# design.net
KiCad netlist of a schematic drawn in Altium Designer
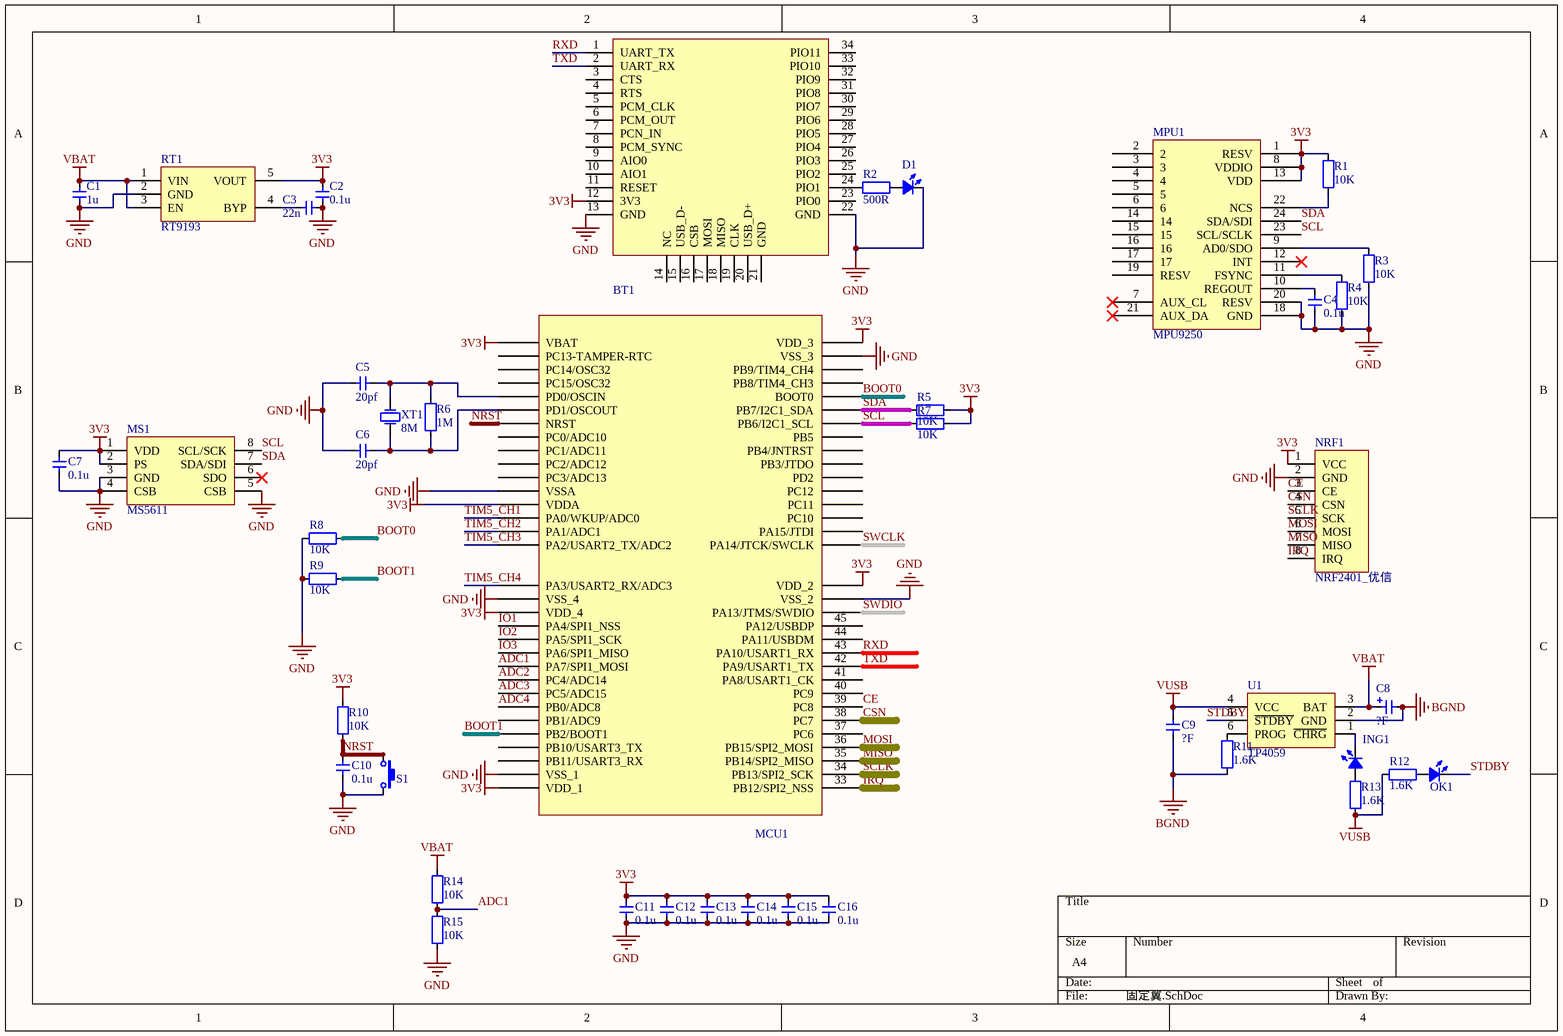
[diagram p0: 固定翼.SchDoc]

(export (version "E")
  (design (tool "Eeschema 10.0.6"))
  (components
    (comp (ref "BT1")
      (value "Bluetooth_HC05")
      (footprint "PCB_Module:Bluetooth_HC05")
      (description "Module")
      (libsource (lib "SCH_Module") (part "Bluetooth_HC05"))
    )
    (comp (ref "C1")
      (value "1u")
      (footprint "PCB_PassiveCap:CAP_0603")
      (description "Capacitor")
      (fields (field (name "Comment") "Cap_0603"))
      (libsource (lib "SCH_Passive") (part "Cap_0603"))
    )
    (comp (ref "C2")
      (value "0.1u")
      (footprint "PCB_PassiveCap:CAP_0603")
      (description "Capacitor")
      (fields (field (name "Comment") "Cap_0603"))
      (libsource (lib "SCH_Passive") (part "Cap_0603"))
    )
    (comp (ref "C3")
      (value "22n")
      (footprint "PCB_PassiveCap:CAP_0603")
      (description "Capacitor")
      (fields (field (name "Comment") "Cap_0603"))
      (libsource (lib "SCH_Passive") (part "Cap_0603"))
    )
    (comp (ref "C4")
      (value "0.1u")
      (footprint "PCB_PassiveCap:CAP_0603")
      (description "Capacitor")
      (fields (field (name "Comment") "Cap_0603"))
      (libsource (lib "SCH_Passive") (part "Cap_0603"))
    )
    (comp (ref "C5")
      (value "20pf")
      (footprint "PCB_PassiveCap:CAP_0603")
      (description "Capacitor")
      (fields (field (name "Comment") "Cap_0603"))
      (libsource (lib "SCH_Passive") (part "Cap_0603"))
    )
    (comp (ref "C6")
      (value "20pf")
      (footprint "PCB_PassiveCap:CAP_0603")
      (description "Capacitor")
      (fields (field (name "Comment") "Cap_0603"))
      (libsource (lib "SCH_Passive") (part "Cap_0603"))
    )
    (comp (ref "C7")
      (value "0.1u")
      (footprint "PCB_PassiveCap:CAP_0603")
      (description "Capacitor")
      (fields (field (name "Comment") "Cap_0603"))
      (libsource (lib "SCH_Passive") (part "Cap_0603"))
    )
    (comp (ref "C8")
      (value "?F")
      (footprint "PCB_PassiveCap:CAP_TAN_D2917")
      (description "Capacitor")
      (fields (field (name "Comment") "Cap_Tan_2917"))
      (libsource (lib "SCH_Passive") (part "Cap_Tan_2917"))
    )
    (comp (ref "C9")
      (value "?F")
      (footprint "PCB_PassiveCap:CAP_0805")
      (description "Capacitor")
      (fields (field (name "Comment") "Cap_0805"))
      (libsource (lib "SCH_Passive") (part "Cap_0805"))
    )
    (comp (ref "C10")
      (value "0.1u")
      (footprint "PCB_PassiveCap:CAP_0603")
      (description "Capacitor")
      (fields (field (name "Comment") "Cap_0603"))
      (libsource (lib "SCH_Passive") (part "Cap_0603"))
    )
    (comp (ref "C11")
      (value "0.1u")
      (footprint "PCB_PassiveCap:CAP_0603")
      (description "Capacitor")
      (fields (field (name "Comment") "Cap_0603"))
      (libsource (lib "SCH_Passive") (part "Cap_0603"))
    )
    (comp (ref "C12")
      (value "0.1u")
      (footprint "PCB_PassiveCap:CAP_0603")
      (description "Capacitor")
      (fields (field (name "Comment") "Cap_0603"))
      (libsource (lib "SCH_Passive") (part "Cap_0603"))
    )
    (comp (ref "C13")
      (value "0.1u")
      (footprint "PCB_PassiveCap:CAP_0603")
      (description "Capacitor")
      (fields (field (name "Comment") "Cap_0603"))
      (libsource (lib "SCH_Passive") (part "Cap_0603"))
    )
    (comp (ref "C14")
      (value "0.1u")
      (footprint "PCB_PassiveCap:CAP_0603")
      (description "Capacitor")
      (fields (field (name "Comment") "Cap_0603"))
      (libsource (lib "SCH_Passive") (part "Cap_0603"))
    )
    (comp (ref "C15")
      (value "0.1u")
      (footprint "PCB_PassiveCap:CAP_0603")
      (description "Capacitor")
      (fields (field (name "Comment") "Cap_0603"))
      (libsource (lib "SCH_Passive") (part "Cap_0603"))
    )
    (comp (ref "C16")
      (value "0.1u")
      (footprint "PCB_PassiveCap:CAP_0603")
      (description "Capacitor")
      (fields (field (name "Comment") "Cap_0603"))
      (libsource (lib "SCH_Passive") (part "Cap_0603"))
    )
    (comp (ref "D1")
      (value "LED_0805")
      (footprint "PCB_ActiveLED:LED_0805_BLUE")
      (description "LED")
      (libsource (lib "SCH_Active") (part "LED_0805"))
    )
    (comp (ref "ING1")
      (value "LED_0805")
      (footprint "PCB_ActiveLED:LED_0805_RED")
      (description "LED")
      (libsource (lib "SCH_Active") (part "LED_0805"))
    )
    (comp (ref "MCU1")
      (value "STM32F103RC")
      (footprint "LQFP_P0.5_64")
      (description "MCU")
      (libsource (lib "SCH_IntegratedCircuit") (part "STM32F103RC"))
    )
    (comp (ref "MPU1")
      (value "MPU9250")
      (footprint "QFN_P0.4_24")
      (libsource (lib "K60-mainboard-v3.1") (part "MPU9250"))
    )
    (comp (ref "MS1")
      (value "MS5611")
      (footprint "PCB_IntegratedCircuit:OTHER_MS5611_8")
      (description "Sensor")
      (libsource (lib "SCH_IntegratedCircuit") (part "MS5611"))
    )
    (comp (ref "NRF1")
      (value "NRF2401_优信")
      (footprint "nrf24l01_youxin")
      (libsource (lib "SCH_Module") (part "NRF2401_优信"))
    )
    (comp (ref "OK1")
      (value "LED_0805")
      (footprint "PCB_ActiveLED:LED_0805_GREEN")
      (description "LED")
      (libsource (lib "SCH_Active") (part "LED_0805"))
    )
    (comp (ref "R1")
      (value "10K")
      (footprint "PCB_PassiveRes:RES_0603")
      (description "Resistor")
      (fields (field (name "Comment") "Res_0603"))
      (libsource (lib "") (part "Res_0603_1"))
    )
    (comp (ref "R2")
      (value "500R")
      (footprint "PCB_PassiveRes:RES_0603")
      (description "Resistor")
      (fields (field (name "Comment") "Res_0603"))
      (libsource (lib "SCH_Passive") (part "Res_0603"))
    )
    (comp (ref "R3")
      (value "10K")
      (footprint "PCB_PassiveRes:RES_0603")
      (description "Resistor")
      (fields (field (name "Comment") "Res_0603"))
      (libsource (lib "") (part "Res_0603_1"))
    )
    (comp (ref "R4")
      (value "10K")
      (footprint "PCB_PassiveRes:RES_0603")
      (description "Resistor")
      (fields (field (name "Comment") "Res_0603"))
      (libsource (lib "") (part "Res_0603_1"))
    )
    (comp (ref "R5")
      (value "10K")
      (footprint "PCB_PassiveRes:RES_0603")
      (description "Resistor")
      (fields (field (name "Comment") "Res_0603"))
      (libsource (lib "SCH_Passive") (part "Res_0603"))
    )
    (comp (ref "R6")
      (value "1M")
      (footprint "PCB_PassiveRes:RES_0603")
      (description "Resistor")
      (fields (field (name "Comment") "Res_0603"))
      (libsource (lib "") (part "Res_0603_2"))
    )
    (comp (ref "R7")
      (value "10K")
      (footprint "PCB_PassiveRes:RES_0603")
      (description "Resistor")
      (fields (field (name "Comment") "Res_0603"))
      (libsource (lib "SCH_Passive") (part "Res_0603"))
    )
    (comp (ref "R8")
      (value "10K")
      (footprint "PCB_PassiveRes:RES_0603")
      (description "Resistor")
      (fields (field (name "Comment") "Res_0603"))
      (libsource (lib "") (part "Res_0603_3"))
    )
    (comp (ref "R9")
      (value "10K")
      (footprint "PCB_PassiveRes:RES_0603")
      (description "Resistor")
      (fields (field (name "Comment") "Res_0603"))
      (libsource (lib "") (part "Res_0603_3"))
    )
    (comp (ref "R10")
      (value "10K")
      (footprint "PCB_PassiveRes:RES_0603")
      (description "Resistor")
      (fields (field (name "Comment") "Res_0603"))
      (libsource (lib "") (part "Res_0603_1"))
    )
    (comp (ref "R11")
      (value "1.6K")
      (footprint "PCB_PassiveRes:RES_0603")
      (description "Resistor")
      (fields (field (name "Comment") "Res_0603"))
      (libsource (lib "") (part "Res_0603_1"))
    )
    (comp (ref "R12")
      (value "1.6K")
      (footprint "PCB_PassiveRes:RES_0603")
      (description "Resistor")
      (fields (field (name "Comment") "Res_0603"))
      (libsource (lib "SCH_Passive") (part "Res_0603"))
    )
    (comp (ref "R13")
      (value "1.6K")
      (footprint "PCB_PassiveRes:RES_0603")
      (description "Resistor")
      (fields (field (name "Comment") "Res_0603"))
      (libsource (lib "") (part "Res_0603_1"))
    )
    (comp (ref "R14")
      (value "10K")
      (footprint "PCB_PassiveRes:RES_0603")
      (description "Resistor")
      (fields (field (name "Comment") "Res_0603"))
      (libsource (lib "") (part "Res_0603_2"))
    )
    (comp (ref "R15")
      (value "10K")
      (footprint "PCB_PassiveRes:RES_0603")
      (description "Resistor")
      (fields (field (name "Comment") "Res_0603"))
      (libsource (lib "") (part "Res_0603_2"))
    )
    (comp (ref "RT1")
      (value "RT9193")
      (footprint "PCB_IntegratedCircuit:SOT23-5")
      (description "Power")
      (libsource (lib "SCH_IntegratedCircuit") (part "RT9193"))
    )
    (comp (ref "S1")
      (value "ButtonTACT_3x4x2_180")
      (footprint "PCB_Switch:ButtonTACT_3x4x2_180H")
      (description "Button")
      (libsource (lib "SCH_Switch") (part "ButtonTACT_3x4x2_180"))
    )
    (comp (ref "U1")
      (value "TP4059")
      (footprint "SOT23-6")
      (libsource (lib "SCH_IntegratedCircuit") (part "TP4059"))
    )
    (comp (ref "XT1")
      (value "8M")
      (footprint "PCB_Oscillator:XT_5032_2")
      (description "Crystal Oscillator")
      (fields (field (name "Comment") "XTAL_5032_2P"))
      (libsource (lib "SCH_Oscillator") (part "XTAL_5032_2P"))
    )
  )
  (nets
    (net (code "1") (name "/ADC1") (class "Default")
      (node (ref "MCU1") (pin "23") (pinfunction "PA7/SPI1_MOSI_23") (pintype "passive"))
      (node (ref "R14") (pin "1") (pinfunction "1_1") (pintype "passive"))
      (node (ref "R15") (pin "2") (pinfunction "2_2") (pintype "passive"))
    )
    (net (code "2") (name "/ADC2") (class "Default")
      (node (ref "MCU1") (pin "24") (pinfunction "PC4/ADC14_24") (pintype "passive"))
    )
    (net (code "3") (name "/ADC3") (class "Default")
      (node (ref "MCU1") (pin "25") (pinfunction "PC5/ADC15_25") (pintype "passive"))
    )
    (net (code "4") (name "/ADC4") (class "Default")
      (node (ref "MCU1") (pin "26") (pinfunction "PB0/ADC8_26") (pintype "passive"))
    )
    (net (code "5") (name "/BOOT0") (class "Default")
      (node (ref "MCU1") (pin "60") (pinfunction "BOOT0_60") (pintype "passive"))
      (node (ref "R8") (pin "1") (pinfunction "1_1") (pintype "passive"))
    )
    (net (code "6") (name "/BOOT1") (class "Default")
      (node (ref "MCU1") (pin "28") (pinfunction "PB2/BOOT1_28") (pintype "passive"))
      (node (ref "R9") (pin "1") (pinfunction "1_1") (pintype "passive"))
    )
    (net (code "7") (name "/CE") (class "Default")
      (node (ref "MCU1") (pin "39") (pinfunction "PC8_39") (pintype "passive"))
      (node (ref "NRF1") (pin "3") (pinfunction "CE_3") (pintype "passive"))
    )
    (net (code "8") (name "/CSN") (class "Default")
      (node (ref "MCU1") (pin "38") (pinfunction "PC7_38") (pintype "passive"))
      (node (ref "NRF1") (pin "4") (pinfunction "CSN_4") (pintype "passive"))
    )
    (net (code "9") (name "/IO1") (class "Default")
      (node (ref "MCU1") (pin "20") (pinfunction "PA4/SPI1_NSS_20") (pintype "passive"))
    )
    (net (code "10") (name "/IO2") (class "Default")
      (node (ref "MCU1") (pin "21") (pinfunction "PA5/SPI1_SCK_21") (pintype "passive"))
    )
    (net (code "11") (name "/IO3") (class "Default")
      (node (ref "MCU1") (pin "22") (pinfunction "PA6/SPI1_MISO_22") (pintype "passive"))
    )
    (net (code "12") (name "/IRQ") (class "Default")
      (node (ref "MCU1") (pin "33") (pinfunction "PB12/SPI2_NSS_33") (pintype "passive"))
      (node (ref "NRF1") (pin "8") (pinfunction "IRQ_8") (pintype "passive"))
    )
    (net (code "13") (name "/MISO") (class "Default")
      (node (ref "MCU1") (pin "35") (pinfunction "PB14/SPI2_MISO_35") (pintype "passive"))
      (node (ref "NRF1") (pin "7") (pinfunction "MISO_7") (pintype "passive"))
    )
    (net (code "14") (name "/MOSI") (class "Default")
      (node (ref "MCU1") (pin "36") (pinfunction "PB15/SPI2_MOSI_36") (pintype "passive"))
      (node (ref "NRF1") (pin "6") (pinfunction "MOSI_6") (pintype "passive"))
    )
    (net (code "15") (name "/NRST") (class "Default")
      (node (ref "C10") (pin "2") (pinfunction "2_2") (pintype "passive"))
      (node (ref "MCU1") (pin "7") (pinfunction "NRST_7") (pintype "passive"))
      (node (ref "R10") (pin "2") (pinfunction "2_2") (pintype "passive"))
      (node (ref "S1") (pin "1") (pinfunction "1_1") (pintype "passive"))
    )
    (net (code "16") (name "/RXD") (class "Default")
      (node (ref "BT1") (pin "1") (pinfunction "UART_TX_1") (pintype "passive"))
      (node (ref "MCU1") (pin "43") (pinfunction "PA10/USART1_RX_43") (pintype "passive"))
    )
    (net (code "17") (name "/SCL") (class "Default")
      (node (ref "MCU1") (pin "58") (pinfunction "PB6/I2C1_SCL_58") (pintype "passive"))
      (node (ref "MPU1") (pin "23") (pinfunction "SCL/SCLK_23") (pintype "passive"))
      (node (ref "MS1") (pin "8") (pinfunction "SCL/SCK_8") (pintype "passive"))
      (node (ref "R7") (pin "1") (pinfunction "1_1") (pintype "passive"))
    )
    (net (code "18") (name "/SCLK") (class "Default")
      (node (ref "MCU1") (pin "34") (pinfunction "PB13/SPI2_SCK_34") (pintype "passive"))
      (node (ref "NRF1") (pin "5") (pinfunction "SCK_5") (pintype "passive"))
    )
    (net (code "19") (name "/SDA") (class "Default")
      (node (ref "MCU1") (pin "59") (pinfunction "PB7/I2C1_SDA_59") (pintype "passive"))
      (node (ref "MPU1") (pin "24") (pinfunction "SDA/SDI_24") (pintype "passive"))
      (node (ref "MS1") (pin "7") (pinfunction "SDA/SDI_7") (pintype "passive"))
      (node (ref "R5") (pin "1") (pinfunction "1_1") (pintype "passive"))
    )
    (net (code "20") (name "/STDBY") (class "Default")
      (node (ref "OK1") (pin "2") (pinfunction "K_2") (pintype "passive"))
      (node (ref "U1") (pin "5") (pinfunction "~{STDBY}_5") (pintype "passive"))
    )
    (net (code "21") (name "/SWCLK") (class "Default")
      (node (ref "MCU1") (pin "49") (pinfunction "PA14/JTCK/SWCLK_49") (pintype "passive"))
    )
    (net (code "22") (name "/SWDIO") (class "Default")
      (node (ref "MCU1") (pin "46") (pinfunction "PA13/JTMS/SWDIO_46") (pintype "passive"))
    )
    (net (code "23") (name "/TIM5_CH1") (class "Default")
      (node (ref "MCU1") (pin "14") (pinfunction "PA0/WKUP/ADC0_14") (pintype "passive"))
    )
    (net (code "24") (name "/TIM5_CH2") (class "Default")
      (node (ref "MCU1") (pin "15") (pinfunction "PA1/ADC1_15") (pintype "passive"))
    )
    (net (code "25") (name "/TIM5_CH3") (class "Default")
      (node (ref "MCU1") (pin "16") (pinfunction "PA2/USART2_TX/ADC2_16") (pintype "passive"))
    )
    (net (code "26") (name "/TIM5_CH4") (class "Default")
      (node (ref "MCU1") (pin "17") (pinfunction "PA3/USART2_RX/ADC3_17") (pintype "passive"))
    )
    (net (code "27") (name "/TXD") (class "Default")
      (node (ref "BT1") (pin "2") (pinfunction "UART_RX_2") (pintype "passive"))
      (node (ref "MCU1") (pin "42") (pinfunction "PA9/USART1_TX_42") (pintype "passive"))
    )
    (net (code "28") (name "3V3") (class "Default")
      (node (ref "BT1") (pin "12") (pinfunction "3V3_12") (pintype "passive"))
      (node (ref "C11") (pin "2") (pinfunction "2_2") (pintype "passive"))
      (node (ref "C12") (pin "2") (pinfunction "2_2") (pintype "passive"))
      (node (ref "C13") (pin "2") (pinfunction "2_2") (pintype "passive"))
      (node (ref "C14") (pin "2") (pinfunction "2_2") (pintype "passive"))
      (node (ref "C15") (pin "2") (pinfunction "2_2") (pintype "passive"))
      (node (ref "C16") (pin "2") (pinfunction "2_2") (pintype "passive"))
      (node (ref "C2") (pin "2") (pinfunction "2_2") (pintype "passive"))
      (node (ref "C7") (pin "2") (pinfunction "2_2") (pintype "passive"))
      (node (ref "MCU1") (pin "1") (pinfunction "VBAT_1") (pintype "passive"))
      (node (ref "MCU1") (pin "13") (pinfunction "VDDA_13") (pintype "passive"))
      (node (ref "MCU1") (pin "19") (pinfunction "VDD_4_19") (pintype "passive"))
      (node (ref "MCU1") (pin "32") (pinfunction "VDD_1_32") (pintype "passive"))
      (node (ref "MCU1") (pin "48") (pinfunction "VDD_2_48") (pintype "passive"))
      (node (ref "MCU1") (pin "64") (pinfunction "VDD_3_64") (pintype "passive"))
      (node (ref "MPU1") (pin "1") (pinfunction "RESV_1") (pintype "passive"))
      (node (ref "MPU1") (pin "13") (pinfunction "VDD_13") (pintype "passive"))
      (node (ref "MPU1") (pin "8") (pinfunction "VDDIO_8") (pintype "passive"))
      (node (ref "MS1") (pin "1") (pinfunction "VDD_1") (pintype "passive"))
      (node (ref "MS1") (pin "2") (pinfunction "PS_2") (pintype "passive"))
      (node (ref "NRF1") (pin "1") (pinfunction "VCC_1") (pintype "passive"))
      (node (ref "R1") (pin "1") (pinfunction "1_1") (pintype "passive"))
      (node (ref "R10") (pin "1") (pinfunction "1_1") (pintype "passive"))
      (node (ref "R5") (pin "2") (pinfunction "2_2") (pintype "passive"))
      (node (ref "R7") (pin "2") (pinfunction "2_2") (pintype "passive"))
      (node (ref "RT1") (pin "5") (pinfunction "VOUT_5") (pintype "passive"))
    )
    (net (code "29") (name "BGND") (class "Default")
      (node (ref "C8") (pin "2") (pinfunction "2_2") (pintype "passive"))
      (node (ref "C9") (pin "1") (pinfunction "1_1") (pintype "passive"))
      (node (ref "R11") (pin "2") (pinfunction "2_2") (pintype "passive"))
      (node (ref "U1") (pin "2") (pinfunction "GND_2") (pintype "passive"))
    )
    (net (code "30") (name "GND") (class "Default")
      (node (ref "BT1") (pin "13") (pinfunction "GND_13") (pintype "passive"))
      (node (ref "BT1") (pin "22") (pinfunction "GND_22") (pintype "passive"))
      (node (ref "C1") (pin "1") (pinfunction "1_1") (pintype "passive"))
      (node (ref "C10") (pin "1") (pinfunction "1_1") (pintype "passive"))
      (node (ref "C11") (pin "1") (pinfunction "1_1") (pintype "passive"))
      (node (ref "C12") (pin "1") (pinfunction "1_1") (pintype "passive"))
      (node (ref "C13") (pin "1") (pinfunction "1_1") (pintype "passive"))
      (node (ref "C14") (pin "1") (pinfunction "1_1") (pintype "passive"))
      (node (ref "C15") (pin "1") (pinfunction "1_1") (pintype "passive"))
      (node (ref "C16") (pin "1") (pinfunction "1_1") (pintype "passive"))
      (node (ref "C2") (pin "1") (pinfunction "1_1") (pintype "passive"))
      (node (ref "C3") (pin "1") (pinfunction "1_1") (pintype "passive"))
      (node (ref "C4") (pin "2") (pinfunction "2_2") (pintype "passive"))
      (node (ref "C5") (pin "1") (pinfunction "1_1") (pintype "passive"))
      (node (ref "C6") (pin "1") (pinfunction "1_1") (pintype "passive"))
      (node (ref "C7") (pin "1") (pinfunction "1_1") (pintype "passive"))
      (node (ref "D1") (pin "2") (pinfunction "K_2") (pintype "passive"))
      (node (ref "MCU1") (pin "12") (pinfunction "VSSA_12") (pintype "passive"))
      (node (ref "MCU1") (pin "18") (pinfunction "VSS_4_18") (pintype "passive"))
      (node (ref "MCU1") (pin "31") (pinfunction "VSS_1_31") (pintype "passive"))
      (node (ref "MCU1") (pin "47") (pinfunction "VSS_2_47") (pintype "passive"))
      (node (ref "MCU1") (pin "63") (pinfunction "VSS_3_63") (pintype "passive"))
      (node (ref "MPU1") (pin "18") (pinfunction "GND_18") (pintype "passive"))
      (node (ref "MPU1") (pin "20") (pinfunction "RESV_20") (pintype "passive"))
      (node (ref "MS1") (pin "3") (pinfunction "GND_3") (pintype "passive"))
      (node (ref "MS1") (pin "4") (pinfunction "CSB_4") (pintype "passive"))
      (node (ref "MS1") (pin "5") (pinfunction "CSB_5") (pintype "passive"))
      (node (ref "NRF1") (pin "2") (pinfunction "GND_2") (pintype "passive"))
      (node (ref "R15") (pin "1") (pinfunction "1_1") (pintype "passive"))
      (node (ref "R3") (pin "2") (pinfunction "2_2") (pintype "passive"))
      (node (ref "R4") (pin "2") (pinfunction "2_2") (pintype "passive"))
      (node (ref "R8") (pin "2") (pinfunction "2_2") (pintype "passive"))
      (node (ref "R9") (pin "2") (pinfunction "2_2") (pintype "passive"))
      (node (ref "RT1") (pin "2") (pinfunction "GND_2") (pintype "passive"))
      (node (ref "S1") (pin "2") (pinfunction "2_2") (pintype "passive"))
    )
    (net (code "31") (name "Net-(BT1-PIO1)") (class "Default")
      (node (ref "BT1") (pin "24") (pinfunction "PIO1_24") (pintype "passive"))
      (node (ref "R2") (pin "1") (pinfunction "1_1") (pintype "passive"))
    )
    (net (code "32") (name "Net-(D1-A)") (class "Default")
      (node (ref "D1") (pin "1") (pinfunction "A_1") (pintype "passive"))
      (node (ref "R2") (pin "2") (pinfunction "2_2") (pintype "passive"))
    )
    (net (code "33") (name "Net-(ING1-A)") (class "Default")
      (node (ref "ING1") (pin "1") (pinfunction "A_1") (pintype "passive"))
      (node (ref "R13") (pin "1") (pinfunction "1_1") (pintype "passive"))
    )
    (net (code "34") (name "Net-(ING1-K)") (class "Default")
      (node (ref "ING1") (pin "2") (pinfunction "K_2") (pintype "passive"))
      (node (ref "U1") (pin "1") (pinfunction "~{CHRG}_1") (pintype "passive"))
    )
    (net (code "35") (name "Net-(MCU1-PD0{slash}OSCIN)") (class "Default")
      (node (ref "C5") (pin "2") (pinfunction "2_2") (pintype "passive"))
      (node (ref "MCU1") (pin "5") (pinfunction "PD0/OSCIN_5") (pintype "passive"))
      (node (ref "R6") (pin "2") (pinfunction "2_2") (pintype "passive"))
      (node (ref "XT1") (pin "2") (pinfunction "OSC2_2") (pintype "passive"))
    )
    (net (code "36") (name "Net-(MCU1-PD1{slash}OSCOUT)") (class "Default")
      (node (ref "C6") (pin "2") (pinfunction "2_2") (pintype "passive"))
      (node (ref "MCU1") (pin "6") (pinfunction "PD1/OSCOUT_6") (pintype "passive"))
      (node (ref "R6") (pin "1") (pinfunction "1_1") (pintype "passive"))
      (node (ref "XT1") (pin "1") (pinfunction "OSC1_1") (pintype "passive"))
    )
    (net (code "37") (name "Net-(MPU1-AD0{slash}SDO)") (class "Default")
      (node (ref "MPU1") (pin "9") (pinfunction "AD0/SDO_9") (pintype "passive"))
      (node (ref "R3") (pin "1") (pinfunction "1_1") (pintype "passive"))
    )
    (net (code "38") (name "Net-(MPU1-FSYNC)") (class "Default")
      (node (ref "MPU1") (pin "11") (pinfunction "FSYNC_11") (pintype "passive"))
      (node (ref "R4") (pin "1") (pinfunction "1_1") (pintype "passive"))
    )
    (net (code "39") (name "Net-(MPU1-NCS)") (class "Default")
      (node (ref "MPU1") (pin "22") (pinfunction "NCS_22") (pintype "passive"))
      (node (ref "R1") (pin "2") (pinfunction "2_2") (pintype "passive"))
    )
    (net (code "40") (name "Net-(MPU1-REGOUT)") (class "Default")
      (node (ref "C4") (pin "1") (pinfunction "1_1") (pintype "passive"))
      (node (ref "MPU1") (pin "10") (pinfunction "REGOUT_10") (pintype "passive"))
    )
    (net (code "41") (name "Net-(OK1-A)") (class "Default")
      (node (ref "OK1") (pin "1") (pinfunction "A_1") (pintype "passive"))
      (node (ref "R12") (pin "2") (pinfunction "2_2") (pintype "passive"))
    )
    (net (code "42") (name "Net-(RT1-BYP)") (class "Default")
      (node (ref "C3") (pin "2") (pinfunction "2_2") (pintype "passive"))
      (node (ref "RT1") (pin "4") (pinfunction "BYP_4") (pintype "passive"))
    )
    (net (code "43") (name "Net-(U1-PROG)") (class "Default")
      (node (ref "R11") (pin "1") (pinfunction "1_1") (pintype "passive"))
      (node (ref "U1") (pin "6") (pinfunction "PROG_6") (pintype "passive"))
    )
    (net (code "44") (name "VBAT") (class "Default")
      (node (ref "C1") (pin "2") (pinfunction "2_2") (pintype "passive"))
      (node (ref "C8") (pin "1") (pinfunction "1_1") (pintype "passive"))
      (node (ref "R14") (pin "2") (pinfunction "2_2") (pintype "passive"))
      (node (ref "RT1") (pin "1") (pinfunction "VIN_1") (pintype "passive"))
      (node (ref "RT1") (pin "3") (pinfunction "EN_3") (pintype "power_in"))
      (node (ref "U1") (pin "3") (pinfunction "BAT_3") (pintype "passive"))
    )
    (net (code "45") (name "VUSB") (class "Default")
      (node (ref "C9") (pin "2") (pinfunction "2_2") (pintype "passive"))
      (node (ref "R12") (pin "1") (pinfunction "1_1") (pintype "passive"))
      (node (ref "R13") (pin "2") (pinfunction "2_2") (pintype "passive"))
      (node (ref "U1") (pin "4") (pinfunction "VCC_4") (pintype "passive"))
    )
    (net (code "46") (name "unconnected-(BT1-AIO0-Pad9)") (class "Default")
      (node (ref "BT1") (pin "9") (pinfunction "AIO0_9") (pintype "passive"))
    )
    (net (code "47") (name "unconnected-(BT1-AIO1-Pad10)") (class "Default")
      (node (ref "BT1") (pin "10") (pinfunction "AIO1_10") (pintype "passive"))
    )
    (net (code "48") (name "unconnected-(BT1-CLK-Pad19)") (class "Default")
      (node (ref "BT1") (pin "19") (pinfunction "CLK_19") (pintype "passive"))
    )
    (net (code "49") (name "unconnected-(BT1-CSB-Pad16)") (class "Default")
      (node (ref "BT1") (pin "16") (pinfunction "CSB_16") (pintype "passive"))
    )
    (net (code "50") (name "unconnected-(BT1-CTS-Pad3)") (class "Default")
      (node (ref "BT1") (pin "3") (pinfunction "CTS_3") (pintype "passive"))
    )
    (net (code "51") (name "unconnected-(BT1-GND-Pad21)") (class "Default")
      (node (ref "BT1") (pin "21") (pinfunction "GND_21") (pintype "passive"))
    )
    (net (code "52") (name "unconnected-(BT1-MISO-Pad18)") (class "Default")
      (node (ref "BT1") (pin "18") (pinfunction "MISO_18") (pintype "passive"))
    )
    (net (code "53") (name "unconnected-(BT1-MOSI-Pad17)") (class "Default")
      (node (ref "BT1") (pin "17") (pinfunction "MOSI_17") (pintype "passive"))
    )
    (net (code "54") (name "unconnected-(BT1-NC-Pad14)") (class "Default")
      (node (ref "BT1") (pin "14") (pinfunction "NC_14") (pintype "passive"))
    )
    (net (code "55") (name "unconnected-(BT1-PCM_CLK-Pad5)") (class "Default")
      (node (ref "BT1") (pin "5") (pinfunction "PCM_CLK_5") (pintype "passive"))
    )
    (net (code "56") (name "unconnected-(BT1-PCM_OUT-Pad6)") (class "Default")
      (node (ref "BT1") (pin "6") (pinfunction "PCM_OUT_6") (pintype "passive"))
    )
    (net (code "57") (name "unconnected-(BT1-PCM_SYNC-Pad8)") (class "Default")
      (node (ref "BT1") (pin "8") (pinfunction "PCM_SYNC_8") (pintype "passive"))
    )
    (net (code "58") (name "unconnected-(BT1-PCN_IN-Pad7)") (class "Default")
      (node (ref "BT1") (pin "7") (pinfunction "PCN_IN_7") (pintype "passive"))
    )
    (net (code "59") (name "unconnected-(BT1-PIO0-Pad23)") (class "Default")
      (node (ref "BT1") (pin "23") (pinfunction "PIO0_23") (pintype "passive"))
    )
    (net (code "60") (name "unconnected-(BT1-PIO2-Pad25)") (class "Default")
      (node (ref "BT1") (pin "25") (pinfunction "PIO2_25") (pintype "passive"))
    )
    (net (code "61") (name "unconnected-(BT1-PIO3-Pad26)") (class "Default")
      (node (ref "BT1") (pin "26") (pinfunction "PIO3_26") (pintype "passive"))
    )
    (net (code "62") (name "unconnected-(BT1-PIO4-Pad27)") (class "Default")
      (node (ref "BT1") (pin "27") (pinfunction "PIO4_27") (pintype "passive"))
    )
    (net (code "63") (name "unconnected-(BT1-PIO5-Pad28)") (class "Default")
      (node (ref "BT1") (pin "28") (pinfunction "PIO5_28") (pintype "passive"))
    )
    (net (code "64") (name "unconnected-(BT1-PIO6-Pad29)") (class "Default")
      (node (ref "BT1") (pin "29") (pinfunction "PIO6_29") (pintype "passive"))
    )
    (net (code "65") (name "unconnected-(BT1-PIO7-Pad30)") (class "Default")
      (node (ref "BT1") (pin "30") (pinfunction "PIO7_30") (pintype "passive"))
    )
    (net (code "66") (name "unconnected-(BT1-PIO8-Pad31)") (class "Default")
      (node (ref "BT1") (pin "31") (pinfunction "PIO8_31") (pintype "passive"))
    )
    (net (code "67") (name "unconnected-(BT1-PIO9-Pad32)") (class "Default")
      (node (ref "BT1") (pin "32") (pinfunction "PIO9_32") (pintype "passive"))
    )
    (net (code "68") (name "unconnected-(BT1-PIO10-Pad33)") (class "Default")
      (node (ref "BT1") (pin "33") (pinfunction "PIO10_33") (pintype "passive"))
    )
    (net (code "69") (name "unconnected-(BT1-PIO11-Pad34)") (class "Default")
      (node (ref "BT1") (pin "34") (pinfunction "PIO11_34") (pintype "passive"))
    )
    (net (code "70") (name "unconnected-(BT1-RESET-Pad11)") (class "Default")
      (node (ref "BT1") (pin "11") (pinfunction "RESET_11") (pintype "passive"))
    )
    (net (code "71") (name "unconnected-(BT1-RTS-Pad4)") (class "Default")
      (node (ref "BT1") (pin "4") (pinfunction "RTS_4") (pintype "passive"))
    )
    (net (code "72") (name "unconnected-(BT1-USB_D+-Pad20)") (class "Default")
      (node (ref "BT1") (pin "20") (pinfunction "USB_D+_20") (pintype "passive"))
    )
    (net (code "73") (name "unconnected-(BT1-USB_D--Pad15)") (class "Default")
      (node (ref "BT1") (pin "15") (pinfunction "USB_D-_15") (pintype "passive"))
    )
    (net (code "74") (name "unconnected-(MCU1-PA8{slash}USART1_CK-Pad41)") (class "Default")
      (node (ref "MCU1") (pin "41") (pinfunction "PA8/USART1_CK_41") (pintype "passive"))
    )
    (net (code "75") (name "unconnected-(MCU1-PA11{slash}USBDM-Pad44)") (class "Default")
      (node (ref "MCU1") (pin "44") (pinfunction "PA11/USBDM_44") (pintype "passive"))
    )
    (net (code "76") (name "unconnected-(MCU1-PA12{slash}USBDP-Pad45)") (class "Default")
      (node (ref "MCU1") (pin "45") (pinfunction "PA12/USBDP_45") (pintype "passive"))
    )
    (net (code "77") (name "unconnected-(MCU1-PA15{slash}JTDI-Pad50)") (class "Default")
      (node (ref "MCU1") (pin "50") (pinfunction "PA15/JTDI_50") (pintype "passive"))
    )
    (net (code "78") (name "unconnected-(MCU1-PB1{slash}ADC9-Pad27)") (class "Default")
      (node (ref "MCU1") (pin "27") (pinfunction "PB1/ADC9_27") (pintype "passive"))
    )
    (net (code "79") (name "unconnected-(MCU1-PB3{slash}JTDO-Pad55)") (class "Default")
      (node (ref "MCU1") (pin "55") (pinfunction "PB3/JTDO_55") (pintype "passive"))
    )
    (net (code "80") (name "unconnected-(MCU1-PB4{slash}JNTRST-Pad56)") (class "Default")
      (node (ref "MCU1") (pin "56") (pinfunction "PB4/JNTRST_56") (pintype "passive"))
    )
    (net (code "81") (name "unconnected-(MCU1-PB5-Pad57)") (class "Default")
      (node (ref "MCU1") (pin "57") (pinfunction "PB5_57") (pintype "passive"))
    )
    (net (code "82") (name "unconnected-(MCU1-PB8{slash}TIM4_CH3-Pad61)") (class "Default")
      (node (ref "MCU1") (pin "61") (pinfunction "PB8/TIM4_CH3_61") (pintype "passive"))
    )
    (net (code "83") (name "unconnected-(MCU1-PB9{slash}TIM4_CH4-Pad62)") (class "Default")
      (node (ref "MCU1") (pin "62") (pinfunction "PB9/TIM4_CH4_62") (pintype "passive"))
    )
    (net (code "84") (name "unconnected-(MCU1-PB10{slash}USART3_TX-Pad29)") (class "Default")
      (node (ref "MCU1") (pin "29") (pinfunction "PB10/USART3_TX_29") (pintype "passive"))
    )
    (net (code "85") (name "unconnected-(MCU1-PB11{slash}USART3_RX-Pad30)") (class "Default")
      (node (ref "MCU1") (pin "30") (pinfunction "PB11/USART3_RX_30") (pintype "passive"))
    )
    (net (code "86") (name "unconnected-(MCU1-PC0{slash}ADC10-Pad8)") (class "Default")
      (node (ref "MCU1") (pin "8") (pinfunction "PC0/ADC10_8") (pintype "passive"))
    )
    (net (code "87") (name "unconnected-(MCU1-PC1{slash}ADC11-Pad9)") (class "Default")
      (node (ref "MCU1") (pin "9") (pinfunction "PC1/ADC11_9") (pintype "passive"))
    )
    (net (code "88") (name "unconnected-(MCU1-PC2{slash}ADC12-Pad10)") (class "Default")
      (node (ref "MCU1") (pin "10") (pinfunction "PC2/ADC12_10") (pintype "passive"))
    )
    (net (code "89") (name "unconnected-(MCU1-PC3{slash}ADC13-Pad11)") (class "Default")
      (node (ref "MCU1") (pin "11") (pinfunction "PC3/ADC13_11") (pintype "passive"))
    )
    (net (code "90") (name "unconnected-(MCU1-PC6-Pad37)") (class "Default")
      (node (ref "MCU1") (pin "37") (pinfunction "PC6_37") (pintype "passive"))
    )
    (net (code "91") (name "unconnected-(MCU1-PC9-Pad40)") (class "Default")
      (node (ref "MCU1") (pin "40") (pinfunction "PC9_40") (pintype "passive"))
    )
    (net (code "92") (name "unconnected-(MCU1-PC10-Pad51)") (class "Default")
      (node (ref "MCU1") (pin "51") (pinfunction "PC10_51") (pintype "passive"))
    )
    (net (code "93") (name "unconnected-(MCU1-PC11-Pad52)") (class "Default")
      (node (ref "MCU1") (pin "52") (pinfunction "PC11_52") (pintype "passive"))
    )
    (net (code "94") (name "unconnected-(MCU1-PC12-Pad53)") (class "Default")
      (node (ref "MCU1") (pin "53") (pinfunction "PC12_53") (pintype "passive"))
    )
    (net (code "95") (name "unconnected-(MCU1-PC13-TAMPER-RTC-Pad2)") (class "Default")
      (node (ref "MCU1") (pin "2") (pinfunction "PC13-TAMPER-RTC_2") (pintype "passive"))
    )
    (net (code "96") (name "unconnected-(MCU1-PC14{slash}OSC32-Pad3)") (class "Default")
      (node (ref "MCU1") (pin "3") (pinfunction "PC14/OSC32_3") (pintype "passive"))
    )
    (net (code "97") (name "unconnected-(MCU1-PC15{slash}OSC32-Pad4)") (class "Default")
      (node (ref "MCU1") (pin "4") (pinfunction "PC15/OSC32_4") (pintype "passive"))
    )
    (net (code "98") (name "unconnected-(MCU1-PD2-Pad54)") (class "Default")
      (node (ref "MCU1") (pin "54") (pinfunction "PD2_54") (pintype "passive"))
    )
    (net (code "99") (name "unconnected-(MPU1-AUX_CL-Pad7)") (class "Default")
      (node (ref "MPU1") (pin "7") (pinfunction "AUX_CL_7") (pintype "passive+no_connect"))
    )
    (net (code "100") (name "unconnected-(MPU1-AUX_DA-Pad21)") (class "Default")
      (node (ref "MPU1") (pin "21") (pinfunction "AUX_DA_21") (pintype "passive+no_connect"))
    )
    (net (code "101") (name "unconnected-(MPU1-INT-Pad12)") (class "Default")
      (node (ref "MPU1") (pin "12") (pinfunction "INT_12") (pintype "passive+no_connect"))
    )
    (net (code "102") (name "unconnected-(MPU1-Pad2)") (class "Default")
      (node (ref "MPU1") (pin "2") (pinfunction "2_2") (pintype "passive"))
    )
    (net (code "103") (name "unconnected-(MPU1-Pad3)") (class "Default")
      (node (ref "MPU1") (pin "3") (pinfunction "3_3") (pintype "passive"))
    )
    (net (code "104") (name "unconnected-(MPU1-Pad4)") (class "Default")
      (node (ref "MPU1") (pin "4") (pinfunction "4_4") (pintype "passive"))
    )
    (net (code "105") (name "unconnected-(MPU1-Pad5)") (class "Default")
      (node (ref "MPU1") (pin "5") (pinfunction "5_5") (pintype "passive"))
    )
    (net (code "106") (name "unconnected-(MPU1-Pad6)") (class "Default")
      (node (ref "MPU1") (pin "6") (pinfunction "6_6") (pintype "passive"))
    )
    (net (code "107") (name "unconnected-(MPU1-Pad14)") (class "Default")
      (node (ref "MPU1") (pin "14") (pinfunction "14_14") (pintype "passive"))
    )
    (net (code "108") (name "unconnected-(MPU1-Pad15)") (class "Default")
      (node (ref "MPU1") (pin "15") (pinfunction "15_15") (pintype "passive"))
    )
    (net (code "109") (name "unconnected-(MPU1-Pad16)") (class "Default")
      (node (ref "MPU1") (pin "16") (pinfunction "16_16") (pintype "passive"))
    )
    (net (code "110") (name "unconnected-(MPU1-Pad17)") (class "Default")
      (node (ref "MPU1") (pin "17") (pinfunction "17_17") (pintype "passive"))
    )
    (net (code "111") (name "unconnected-(MPU1-RESV-Pad19)") (class "Default")
      (node (ref "MPU1") (pin "19") (pinfunction "RESV_19") (pintype "passive"))
    )
    (net (code "112") (name "unconnected-(MS1-SDO-Pad6)") (class "Default")
      (node (ref "MS1") (pin "6") (pinfunction "SDO_6") (pintype "passive+no_connect"))
    )
  )
)
